# W070X.net
KiCad netlist of a schematic drawn in EAGLE
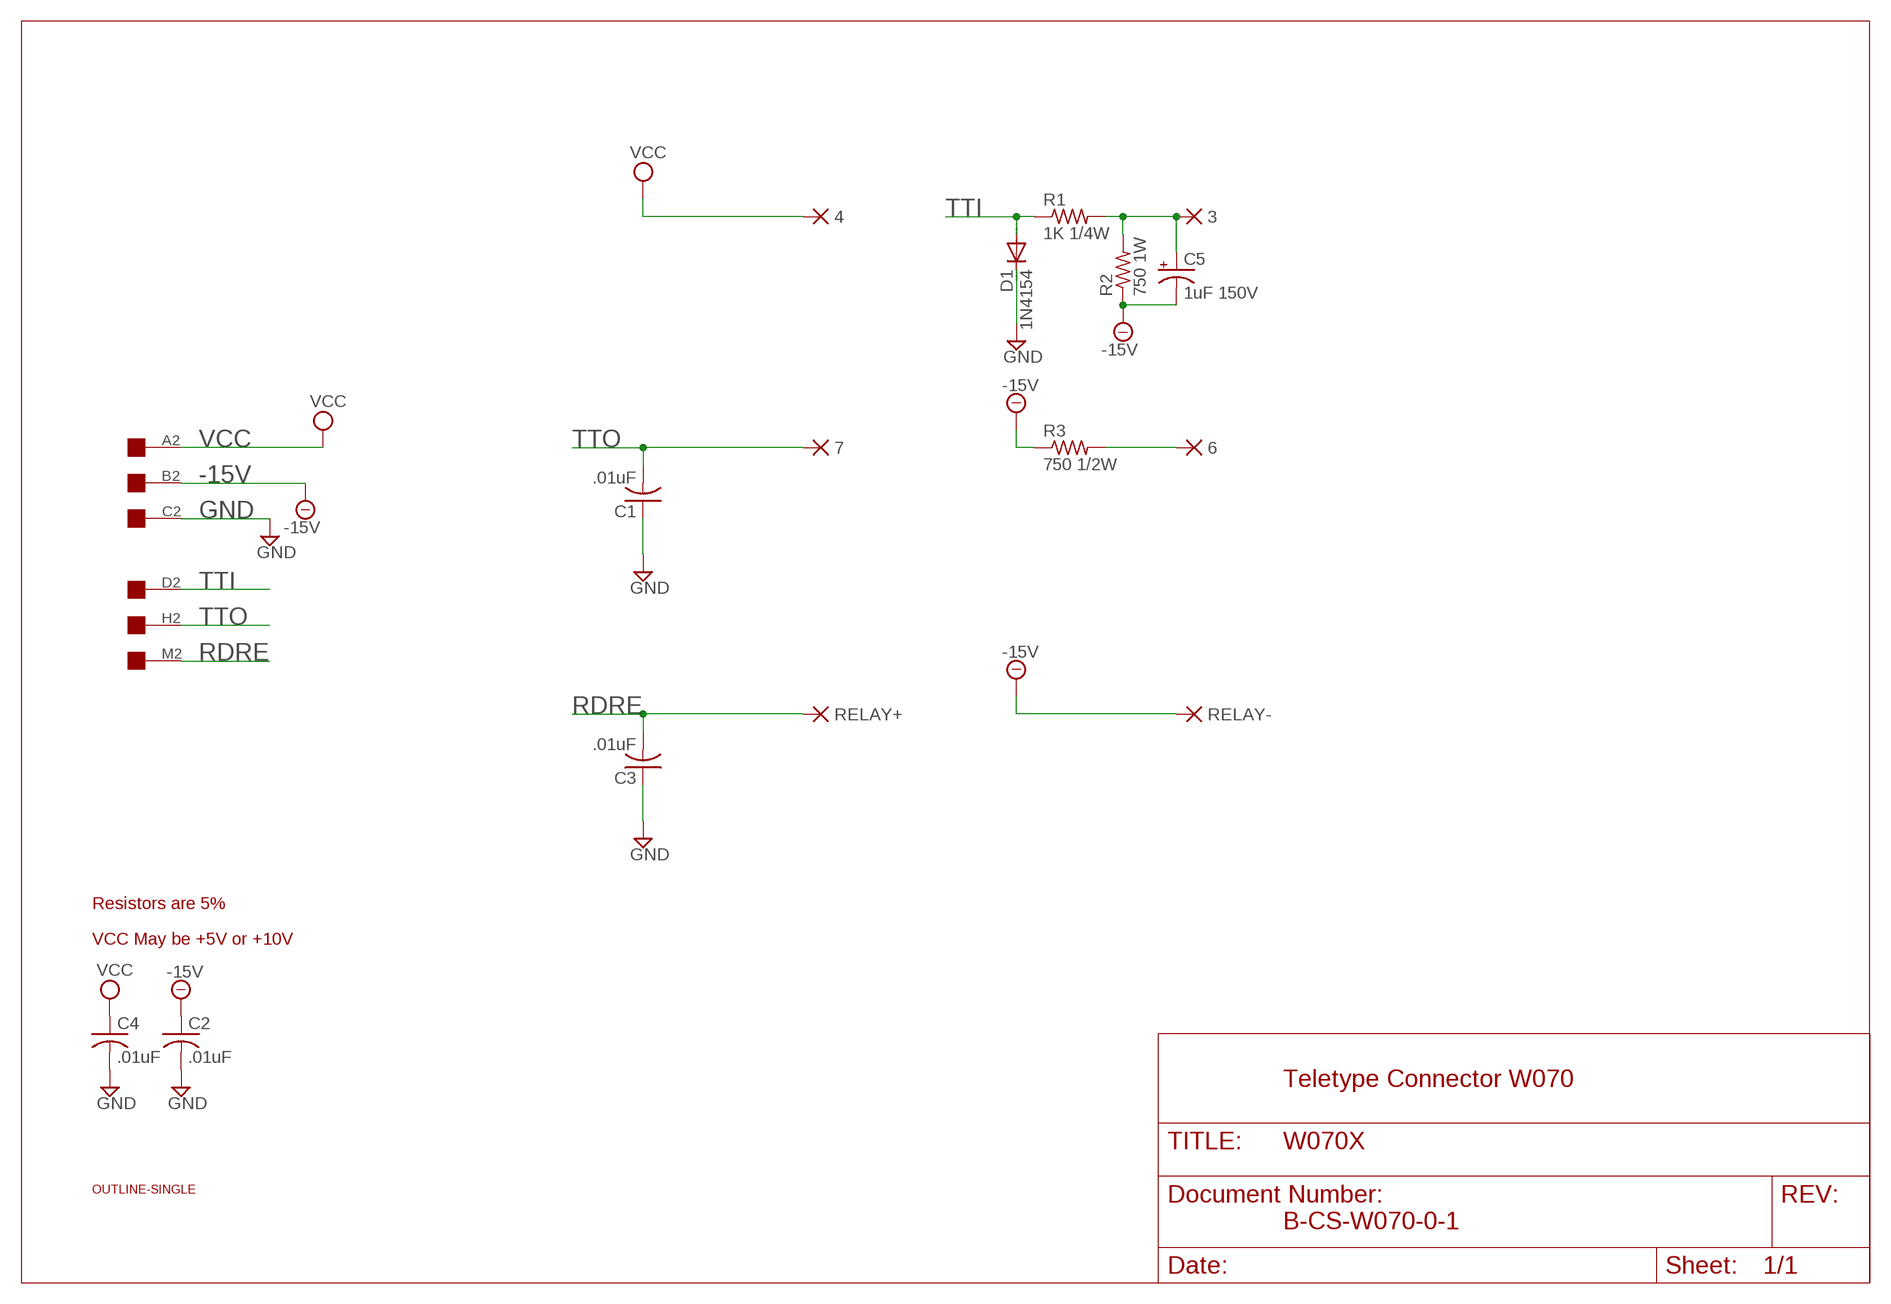
[diagram p0: schematic, sheet 1]

(export (version "E")
  (design (tool "Eeschema 10.0.6"))
  (components
    (comp (ref "3")
      (value "PAD-0465")
      (footprint "eagle-import:0465")
      (libsource (lib "eagle-import") (part "PAD-0465"))
    )
    (comp (ref "4")
      (value "PAD-0465")
      (footprint "eagle-import:0465")
      (libsource (lib "eagle-import") (part "PAD-0465"))
    )
    (comp (ref "6")
      (value "PAD-0465")
      (footprint "eagle-import:0465")
      (libsource (lib "eagle-import") (part "PAD-0465"))
    )
    (comp (ref "7")
      (value "PAD-0465")
      (footprint "eagle-import:0465")
      (libsource (lib "eagle-import") (part "PAD-0465"))
    )
    (comp (ref "C1")
      (value ".01uF")
      (footprint "eagle-import:C050-025X075")
      (libsource (lib "eagle-import") (part "C-US050-025X075"))
    )
    (comp (ref "C2")
      (value ".01uF")
      (footprint "eagle-import:C050-025X075")
      (libsource (lib "eagle-import") (part "C-US050-025X075"))
    )
    (comp (ref "C3")
      (value ".01uF")
      (footprint "eagle-import:C050-025X075")
      (libsource (lib "eagle-import") (part "C-US050-025X075"))
    )
    (comp (ref "C4")
      (value ".01uF")
      (footprint "eagle-import:C050-025X075")
      (libsource (lib "eagle-import") (part "C-US050-025X075"))
    )
    (comp (ref "C5")
      (value "1uF 150V")
      (footprint "eagle-import:E25-9")
      (libsource (lib "eagle-import") (part "CPOL-USE25-9AXIAL"))
    )
    (comp (ref "D1")
      (value "1N4154")
      (footprint "eagle-import:DO35-10")
      (libsource (lib "eagle-import") (part "1N4148DO35-10"))
    )
    (comp (ref "EDGE")
      (value "EDGE-1")
      (footprint "eagle-import:EDGE-CON1")
      (libsource (lib "eagle-import") (part "EDGE-1"))
    )
    (comp (ref "R1")
      (value "1K 1/4W")
      (footprint "eagle-import:0207_10")
      (libsource (lib "eagle-import") (part "R-US_0207/10"))
    )
    (comp (ref "R2")
      (value "750 1W")
      (footprint "eagle-import:0411_12")
      (libsource (lib "eagle-import") (part "R-US_0411/12"))
    )
    (comp (ref "R3")
      (value "750 1/2W")
      (footprint "eagle-import:0309_12")
      (libsource (lib "eagle-import") (part "R-US_0309/12"))
    )
    (comp (ref "RELAY+")
      (value "PAD-0465")
      (footprint "eagle-import:0465")
      (libsource (lib "eagle-import") (part "PAD-0465"))
    )
    (comp (ref "RELAY-")
      (value "PAD-0465")
      (footprint "eagle-import:0465")
      (libsource (lib "eagle-import") (part "PAD-0465"))
    )
    (comp (ref "U$1")
      (value "OUTLINE-SINGLE")
      (footprint "eagle-import:SINGLE")
      (libsource (lib "eagle-import") (part "OUTLINE-SINGLE"))
    )
  )
  (nets
    (net (code "1") (name "-15V") (class "Default")
      (node (ref "C2") (pin "1") (pinfunction "1_1") (pintype "passive"))
      (node (ref "C5") (pin "-") (pinfunction "-_-") (pintype "passive"))
      (node (ref "EDGE") (pin "B2") (pinfunction "1_B2") (pintype "bidirectional"))
      (node (ref "R2") (pin "1") (pinfunction "1_1") (pintype "passive"))
      (node (ref "R3") (pin "1") (pinfunction "1_1") (pintype "passive"))
      (node (ref "RELAY-") (pin "P$1") (pinfunction "P_P$1") (pintype "passive"))
    )
    (net (code "2") (name "/RDRE") (class "Default")
      (node (ref "C3") (pin "2") (pinfunction "2_2") (pintype "passive"))
      (node (ref "EDGE") (pin "M2") (pinfunction "1_M2") (pintype "bidirectional"))
      (node (ref "RELAY+") (pin "P$1") (pinfunction "P_P$1") (pintype "passive"))
    )
    (net (code "3") (name "/TTI") (class "Default")
      (node (ref "D1") (pin "A") (pinfunction "A_A") (pintype "passive"))
      (node (ref "EDGE") (pin "D2") (pinfunction "1_D2") (pintype "bidirectional"))
      (node (ref "R1") (pin "1") (pinfunction "1_1") (pintype "passive"))
    )
    (net (code "4") (name "/TTO") (class "Default")
      (node (ref "7") (pin "P$1") (pinfunction "P_P$1") (pintype "passive"))
      (node (ref "C1") (pin "2") (pinfunction "2_2") (pintype "passive"))
      (node (ref "EDGE") (pin "H2") (pinfunction "1_H2") (pintype "bidirectional"))
    )
    (net (code "5") (name "GND") (class "Default")
      (node (ref "C1") (pin "1") (pinfunction "1_1") (pintype "passive"))
      (node (ref "C2") (pin "2") (pinfunction "2_2") (pintype "passive"))
      (node (ref "C3") (pin "1") (pinfunction "1_1") (pintype "passive"))
      (node (ref "C4") (pin "2") (pinfunction "2_2") (pintype "passive"))
      (node (ref "D1") (pin "C") (pinfunction "C_C") (pintype "passive"))
      (node (ref "EDGE") (pin "C2") (pinfunction "1_C2") (pintype "bidirectional"))
    )
    (net (code "6") (name "Net-(3-P)") (class "Default")
      (node (ref "3") (pin "P$1") (pinfunction "P_P$1") (pintype "passive"))
      (node (ref "C5") (pin "+") (pinfunction "+_+") (pintype "passive"))
      (node (ref "R1") (pin "2") (pinfunction "2_2") (pintype "passive"))
      (node (ref "R2") (pin "2") (pinfunction "2_2") (pintype "passive"))
    )
    (net (code "7") (name "Net-(6-P)") (class "Default")
      (node (ref "6") (pin "P$1") (pinfunction "P_P$1") (pintype "passive"))
      (node (ref "R3") (pin "2") (pinfunction "2_2") (pintype "passive"))
    )
    (net (code "8") (name "VCC") (class "Default")
      (node (ref "4") (pin "P$1") (pinfunction "P_P$1") (pintype "passive"))
      (node (ref "C4") (pin "1") (pinfunction "1_1") (pintype "passive"))
      (node (ref "EDGE") (pin "A2") (pinfunction "1_A2") (pintype "bidirectional"))
    )
  )
)
